# main.net
KiCad netlist of a schematic drawn in EAGLE
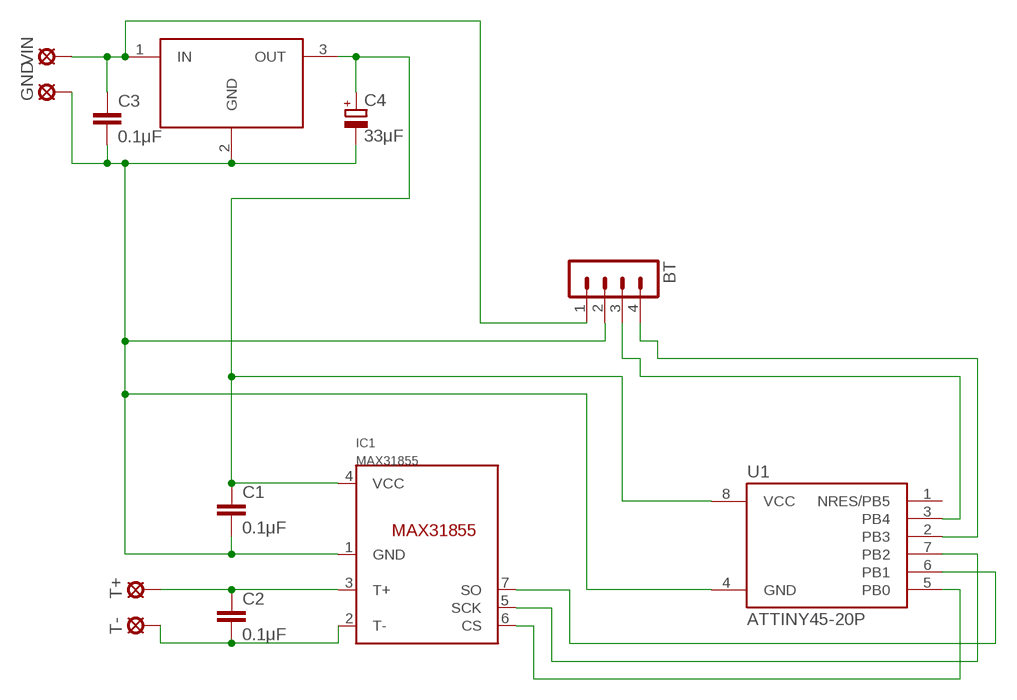
[diagram p0: schematic, sheet 1]

(export (version "E")
  (design (tool "Eeschema 10.0.6"))
  (components
    (comp (ref "BT")
      (value "MA04-1")
      (footprint "eagle-import:MA04-1")
      (libsource (lib "eagle-import") (part "MA04-1"))
    )
    (comp (ref "C1")
      (value "0.1μF")
      (footprint "eagle-import:C1206")
      (libsource (lib "eagle-import") (part "C-EUC1206"))
    )
    (comp (ref "C2")
      (value "0.1μF")
      (footprint "eagle-import:C1206")
      (libsource (lib "eagle-import") (part "C-EUC1206"))
    )
    (comp (ref "C3")
      (value "0.1μF")
      (footprint "eagle-import:C1206")
      (libsource (lib "eagle-import") (part "C-EUC1206"))
    )
    (comp (ref "C4")
      (value "33μF")
      (footprint "eagle-import:E1,8-4")
      (libsource (lib "eagle-import") (part "CPOL-EUE1.8-4"))
    )
    (comp (ref "GND")
      (value "LSP13")
      (footprint "eagle-import:LSP13")
      (libsource (lib "eagle-import") (part "LSP13"))
    )
    (comp (ref "IC1")
      (value "MAX31855")
      (footprint "eagle-import:SOIC8")
      (libsource (lib "eagle-import") (part "MAX31855"))
    )
    (comp (ref "IC2")
      (value "LM3940IMP-3.3")
      (footprint "eagle-import:SOT223")
      (libsource (lib "eagle-import") (part "LM3940IMP-3.3"))
    )
    (comp (ref "T+")
      (value "LSP13")
      (footprint "eagle-import:LSP13")
      (libsource (lib "eagle-import") (part "LSP13"))
    )
    (comp (ref "T-")
      (value "LSP13")
      (footprint "eagle-import:LSP13")
      (libsource (lib "eagle-import") (part "LSP13"))
    )
    (comp (ref "U1")
      (value "ATTINY45-20P")
      (footprint "eagle-import:PDIP08_300MIL")
      (libsource (lib "eagle-import") (part "ATTINY45P-20"))
    )
    (comp (ref "VIN")
      (value "LSP13")
      (footprint "eagle-import:LSP13")
      (libsource (lib "eagle-import") (part "LSP13"))
    )
  )
  (nets
    (net (code "1") (name "Net-(IC1-CS)") (class "Default")
      (node (ref "IC1") (pin "6") (pinfunction "CS_6") (pintype "input"))
      (node (ref "U1") (pin "5") (pinfunction "PB0_5") (pintype "bidirectional"))
    )
    (net (code "2") (name "Net-(IC1-GND)") (class "Default")
      (node (ref "BT") (pin "2") (pinfunction "2_2") (pintype "passive"))
      (node (ref "C1") (pin "2") (pinfunction "2_2") (pintype "passive"))
      (node (ref "C3") (pin "2") (pinfunction "2_2") (pintype "passive"))
      (node (ref "C4") (pin "-") (pinfunction "-_-") (pintype "passive"))
      (node (ref "GND") (pin "MP") (pinfunction "MP_MP") (pintype "passive"))
      (node (ref "IC1") (pin "1") (pinfunction "GND_1") (pintype "power_in"))
      (node (ref "IC2") (pin "2") (pinfunction "GND_2") (pintype "power_in"))
      (node (ref "U1") (pin "4") (pinfunction "GND_4") (pintype "power_in"))
    )
    (net (code "3") (name "Net-(IC1-SCK)") (class "Default")
      (node (ref "IC1") (pin "5") (pinfunction "SCK_5") (pintype "input"))
      (node (ref "U1") (pin "7") (pinfunction "PB2_7") (pintype "bidirectional"))
    )
    (net (code "4") (name "Net-(IC1-SO)") (class "Default")
      (node (ref "IC1") (pin "7") (pinfunction "SO_7") (pintype "output"))
      (node (ref "U1") (pin "6") (pinfunction "PB1_6") (pintype "bidirectional"))
    )
    (net (code "5") (name "Net-(IC1-T+)") (class "Default")
      (node (ref "C2") (pin "1") (pinfunction "1_1") (pintype "passive"))
      (node (ref "IC1") (pin "3") (pinfunction "T+_3") (pintype "input"))
      (node (ref "T+") (pin "MP") (pinfunction "MP_MP") (pintype "passive"))
    )
    (net (code "6") (name "Net-(IC1-T-)") (class "Default")
      (node (ref "C2") (pin "2") (pinfunction "2_2") (pintype "passive"))
      (node (ref "IC1") (pin "2") (pinfunction "T-_2") (pintype "input"))
      (node (ref "T-") (pin "MP") (pinfunction "MP_MP") (pintype "passive"))
    )
    (net (code "7") (name "Net-(IC1-VCC)") (class "Default")
      (node (ref "C1") (pin "1") (pinfunction "1_1") (pintype "passive"))
      (node (ref "C4") (pin "+") (pinfunction "+_+") (pintype "passive"))
      (node (ref "IC1") (pin "4") (pinfunction "VCC_4") (pintype "power_in"))
      (node (ref "IC2") (pin "3") (pinfunction "OUT_3") (pintype "power_in"))
      (node (ref "U1") (pin "8") (pinfunction "VCC_8") (pintype "power_in"))
    )
    (net (code "8") (name "Net-(IC2-IN)") (class "Default")
      (node (ref "BT") (pin "1") (pinfunction "1_1") (pintype "passive"))
      (node (ref "C3") (pin "1") (pinfunction "1_1") (pintype "passive"))
      (node (ref "IC2") (pin "1") (pinfunction "IN_1") (pintype "power_in"))
      (node (ref "VIN") (pin "MP") (pinfunction "MP_MP") (pintype "passive"))
    )
    (net (code "9") (name "Net-(U1-PB3)") (class "Default")
      (node (ref "BT") (pin "4") (pinfunction "4_4") (pintype "passive"))
      (node (ref "U1") (pin "2") (pinfunction "PB3_2") (pintype "bidirectional"))
    )
    (net (code "10") (name "Net-(U1-PB4)") (class "Default")
      (node (ref "BT") (pin "3") (pinfunction "3_3") (pintype "passive"))
      (node (ref "U1") (pin "3") (pinfunction "PB4_3") (pintype "bidirectional"))
    )
    (net (code "11") (name "unconnected-(U1-NRES{slash}PB5-Pad1)") (class "Default")
      (node (ref "U1") (pin "1") (pinfunction "NRES/PB5_1") (pintype "bidirectional"))
    )
  )
)
